# hexbot_LED.net
KiCad netlist of a schematic drawn in Altium Designer
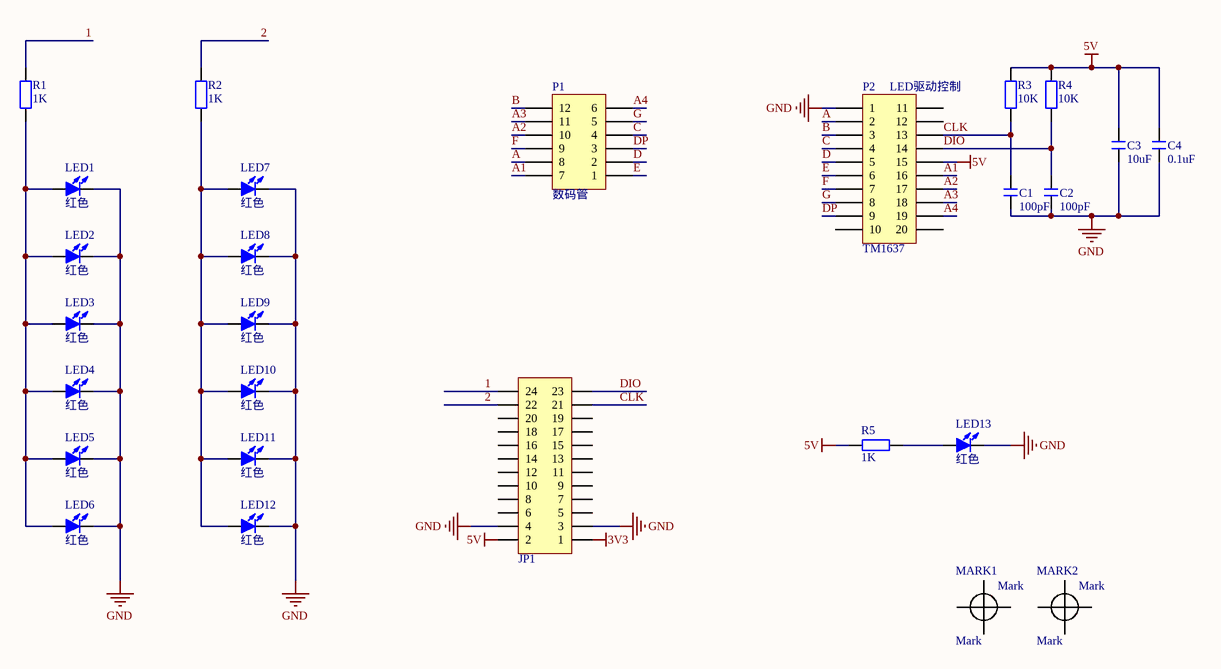
[diagram p0: hexbot_LED.SchDoc]

(export (version "E")
  (design (tool "Eeschema 10.0.6"))
  (components
    (comp (ref "C1")
      (value "100pF")
      (footprint "C 0603_L")
      (description "贴片电容")
      (libsource (lib "0.1 - 电阻-电容-电感") (part "C"))
    )
    (comp (ref "C2")
      (value "100pF")
      (footprint "C 0603_L")
      (description "贴片电容")
      (libsource (lib "0.1 - 电阻-电容-电感") (part "C"))
    )
    (comp (ref "C3")
      (value "10uF")
      (footprint "C 0603_L")
      (description "贴片电容")
      (libsource (lib "0.1 - 电阻-电容-电感") (part "C"))
    )
    (comp (ref "C4")
      (value "0.1uF")
      (footprint "C 0603_L")
      (description "贴片电容")
      (libsource (lib "0.1 - 电阻-电容-电感") (part "C"))
    )
    (comp (ref "JP1")
      (value "Header 2X11")
      (footprint "HDR2.54-WI-2x12P")
      (description "12*2P接插件")
      (fields (field (name "版权归属") "封装库来自淘宝卖家 ID：黄晶宝石"))
      (libsource (lib "5.4 - 接插件-脚距2.54 (100mil) ") (part "Header 12X2"))
    )
    (comp (ref "LED1")
      (value "红色")
      (footprint "LED 0603R")
      (description "贴片LED")
      (fields (field (name "版权归属") "封装库来自淘宝 ID：黄晶宝石"))
      (libsource (lib "0.3 - LED发光二极管") (part "LED-SMD"))
    )
    (comp (ref "LED2")
      (value "红色")
      (footprint "LED 0603R")
      (description "贴片LED")
      (fields (field (name "版权归属") "封装库来自淘宝 ID：黄晶宝石"))
      (libsource (lib "0.3 - LED发光二极管") (part "LED-SMD"))
    )
    (comp (ref "LED3")
      (value "红色")
      (footprint "LED 0603R")
      (description "贴片LED")
      (fields (field (name "版权归属") "封装库来自淘宝 ID：黄晶宝石"))
      (libsource (lib "0.3 - LED发光二极管") (part "LED-SMD"))
    )
    (comp (ref "LED4")
      (value "红色")
      (footprint "LED 0603R")
      (description "贴片LED")
      (fields (field (name "版权归属") "封装库来自淘宝 ID：黄晶宝石"))
      (libsource (lib "0.3 - LED发光二极管") (part "LED-SMD"))
    )
    (comp (ref "LED5")
      (value "红色")
      (footprint "LED 0603R")
      (description "贴片LED")
      (fields (field (name "版权归属") "封装库来自淘宝 ID：黄晶宝石"))
      (libsource (lib "0.3 - LED发光二极管") (part "LED-SMD"))
    )
    (comp (ref "LED6")
      (value "红色")
      (footprint "LED 0603R")
      (description "贴片LED")
      (fields (field (name "版权归属") "封装库来自淘宝 ID：黄晶宝石"))
      (libsource (lib "0.3 - LED发光二极管") (part "LED-SMD"))
    )
    (comp (ref "LED7")
      (value "红色")
      (footprint "LED 0603R")
      (description "贴片LED")
      (fields (field (name "版权归属") "封装库来自淘宝 ID：黄晶宝石"))
      (libsource (lib "0.3 - LED发光二极管") (part "LED-SMD"))
    )
    (comp (ref "LED8")
      (value "红色")
      (footprint "LED 0603R")
      (description "贴片LED")
      (fields (field (name "版权归属") "封装库来自淘宝 ID：黄晶宝石"))
      (libsource (lib "0.3 - LED发光二极管") (part "LED-SMD"))
    )
    (comp (ref "LED9")
      (value "红色")
      (footprint "LED 0603R")
      (description "贴片LED")
      (fields (field (name "版权归属") "封装库来自淘宝 ID：黄晶宝石"))
      (libsource (lib "0.3 - LED发光二极管") (part "LED-SMD"))
    )
    (comp (ref "LED10")
      (value "红色")
      (footprint "LED 0603R")
      (description "贴片LED")
      (fields (field (name "版权归属") "封装库来自淘宝 ID：黄晶宝石"))
      (libsource (lib "0.3 - LED发光二极管") (part "LED-SMD"))
    )
    (comp (ref "LED11")
      (value "红色")
      (footprint "LED 0603R")
      (description "贴片LED")
      (fields (field (name "版权归属") "封装库来自淘宝 ID：黄晶宝石"))
      (libsource (lib "0.3 - LED发光二极管") (part "LED-SMD"))
    )
    (comp (ref "LED12")
      (value "红色")
      (footprint "LED 0603R")
      (description "贴片LED")
      (fields (field (name "版权归属") "封装库来自淘宝 ID：黄晶宝石"))
      (libsource (lib "0.3 - LED发光二极管") (part "LED-SMD"))
    )
    (comp (ref "LED13")
      (value "红色")
      (footprint "LED 0603R")
      (description "贴片LED")
      (fields (field (name "版权归属") "封装库来自淘宝 ID：黄晶宝石"))
      (libsource (lib "0.3 - LED发光二极管") (part "LED-SMD"))
    )
    (comp (ref "MARK1") (value "Mark") (footprint "Mark:Mark") (libsource (lib "Mark") (part "Mark")))
    (comp (ref "MARK2") (value "Mark") (footprint "Mark:Mark") (libsource (lib "Mark") (part "Mark")))
    (comp (ref "P1")
      (value "数码管")
      (footprint "数码管")
      (description "Header, 6-Pin, Dual row")
      (fields (field (name "PUBLISHER") "Altium Limited"))
      (libsource (lib "Miscellaneous Connectors") (part "Header 6X2A"))
    )
    (comp (ref "P2")
      (value "TM1637")
      (footprint "TM1637封装")
      (description "Header, 10-Pin, Dual row")
      (fields (field (name "PUBLISHER") "Altium Limited"))
      (libsource (lib "Miscellaneous Connectors") (part "Header 10X2A"))
    )
    (comp (ref "R1")
      (value "1K")
      (footprint "R 0603_L")
      (description "贴片电阻")
      (fields (field (name "版权归属") "来自淘宝 ID：黄晶宝石"))
      (libsource (lib "0.1 - 电阻-电容-电感") (part "R"))
    )
    (comp (ref "R2")
      (value "1K")
      (footprint "R 0603_L")
      (description "贴片电阻")
      (fields (field (name "版权归属") "来自淘宝 ID：黄晶宝石"))
      (libsource (lib "0.1 - 电阻-电容-电感") (part "R"))
    )
    (comp (ref "R3")
      (value "10K")
      (footprint "R 0603_L")
      (description "贴片电阻")
      (fields (field (name "版权归属") "来自淘宝 ID：黄晶宝石"))
      (libsource (lib "0.1 - 电阻-电容-电感") (part "R"))
    )
    (comp (ref "R4")
      (value "10K")
      (footprint "R 0603_L")
      (description "贴片电阻")
      (fields (field (name "版权归属") "来自淘宝 ID：黄晶宝石"))
      (libsource (lib "0.1 - 电阻-电容-电感") (part "R"))
    )
    (comp (ref "R5")
      (value "1K")
      (footprint "R 0603_L")
      (description "贴片电阻")
      (fields (field (name "版权归属") "来自淘宝 ID：黄晶宝石"))
      (libsource (lib "0.1 - 电阻-电容-电感") (part "R"))
    )
  )
  (nets
    (net (code "1") (name "/1") (class "Default")
      (node (ref "JP1") (pin "24") (pinfunction "24_24") (pintype "passive"))
      (node (ref "R1") (pin "2") (pinfunction "2_2") (pintype "passive"))
    )
    (net (code "2") (name "/2") (class "Default")
      (node (ref "JP1") (pin "22") (pinfunction "22_22") (pintype "passive"))
      (node (ref "R2") (pin "2") (pinfunction "2_2") (pintype "passive"))
    )
    (net (code "3") (name "/A") (class "Default")
      (node (ref "P1") (pin "8") (pinfunction "8_8") (pintype "passive"))
      (node (ref "P2") (pin "2") (pinfunction "2_2") (pintype "passive"))
    )
    (net (code "4") (name "/A1") (class "Default")
      (node (ref "P1") (pin "7") (pinfunction "7_7") (pintype "passive"))
      (node (ref "P2") (pin "16") (pinfunction "16_16") (pintype "passive"))
    )
    (net (code "5") (name "/A2") (class "Default")
      (node (ref "P1") (pin "10") (pinfunction "10_10") (pintype "passive"))
      (node (ref "P2") (pin "17") (pinfunction "17_17") (pintype "passive"))
    )
    (net (code "6") (name "/A3") (class "Default")
      (node (ref "P1") (pin "11") (pinfunction "11_11") (pintype "passive"))
      (node (ref "P2") (pin "18") (pinfunction "18_18") (pintype "passive"))
    )
    (net (code "7") (name "/A4") (class "Default")
      (node (ref "P1") (pin "6") (pinfunction "6_6") (pintype "passive"))
      (node (ref "P2") (pin "19") (pinfunction "19_19") (pintype "passive"))
    )
    (net (code "8") (name "/B") (class "Default")
      (node (ref "P1") (pin "12") (pinfunction "12_12") (pintype "passive"))
      (node (ref "P2") (pin "3") (pinfunction "3_3") (pintype "passive"))
    )
    (net (code "9") (name "/C") (class "Default")
      (node (ref "P1") (pin "4") (pinfunction "4_4") (pintype "passive"))
      (node (ref "P2") (pin "4") (pinfunction "4_4") (pintype "passive"))
    )
    (net (code "10") (name "/CLK") (class "Default")
      (node (ref "C1") (pin "2") (pinfunction "2_2") (pintype "passive"))
      (node (ref "JP1") (pin "21") (pinfunction "21_21") (pintype "passive"))
      (node (ref "P2") (pin "13") (pinfunction "13_13") (pintype "passive"))
      (node (ref "R3") (pin "1") (pinfunction "1_1") (pintype "passive"))
    )
    (net (code "11") (name "/D") (class "Default")
      (node (ref "P1") (pin "2") (pinfunction "2_2") (pintype "passive"))
      (node (ref "P2") (pin "5") (pinfunction "5_5") (pintype "passive"))
    )
    (net (code "12") (name "/DIO") (class "Default")
      (node (ref "C2") (pin "2") (pinfunction "2_2") (pintype "passive"))
      (node (ref "JP1") (pin "23") (pinfunction "23_23") (pintype "passive"))
      (node (ref "P2") (pin "14") (pinfunction "14_14") (pintype "passive"))
      (node (ref "R4") (pin "1") (pinfunction "1_1") (pintype "passive"))
    )
    (net (code "13") (name "/DP") (class "Default")
      (node (ref "P1") (pin "3") (pinfunction "3_3") (pintype "passive"))
      (node (ref "P2") (pin "9") (pinfunction "9_9") (pintype "passive"))
    )
    (net (code "14") (name "/E") (class "Default")
      (node (ref "P1") (pin "1") (pinfunction "1_1") (pintype "passive"))
      (node (ref "P2") (pin "6") (pinfunction "6_6") (pintype "passive"))
    )
    (net (code "15") (name "/F") (class "Default")
      (node (ref "P1") (pin "9") (pinfunction "9_9") (pintype "passive"))
      (node (ref "P2") (pin "7") (pinfunction "7_7") (pintype "passive"))
    )
    (net (code "16") (name "/G") (class "Default")
      (node (ref "P1") (pin "5") (pinfunction "5_5") (pintype "passive"))
      (node (ref "P2") (pin "8") (pinfunction "8_8") (pintype "passive"))
    )
    (net (code "17") (name "3V3") (class "Default")
      (node (ref "JP1") (pin "1") (pinfunction "1_1") (pintype "passive"))
    )
    (net (code "18") (name "5V") (class "Default")
      (node (ref "C3") (pin "2") (pinfunction "2_2") (pintype "passive"))
      (node (ref "C4") (pin "2") (pinfunction "2_2") (pintype "passive"))
      (node (ref "JP1") (pin "2") (pinfunction "2_2") (pintype "passive"))
      (node (ref "P2") (pin "15") (pinfunction "15_15") (pintype "passive"))
      (node (ref "R3") (pin "2") (pinfunction "2_2") (pintype "passive"))
      (node (ref "R4") (pin "2") (pinfunction "2_2") (pintype "passive"))
      (node (ref "R5") (pin "2") (pinfunction "2_2") (pintype "passive"))
    )
    (net (code "19") (name "GND") (class "Default")
      (node (ref "C1") (pin "1") (pinfunction "1_1") (pintype "passive"))
      (node (ref "C2") (pin "1") (pinfunction "1_1") (pintype "passive"))
      (node (ref "C3") (pin "1") (pinfunction "1_1") (pintype "passive"))
      (node (ref "C4") (pin "1") (pinfunction "1_1") (pintype "passive"))
      (node (ref "JP1") (pin "3") (pinfunction "3_3") (pintype "passive"))
      (node (ref "JP1") (pin "4") (pinfunction "4_4") (pintype "passive"))
      (node (ref "LED1") (pin "2") (pinfunction "K_2") (pintype "passive"))
      (node (ref "LED10") (pin "2") (pinfunction "K_2") (pintype "passive"))
      (node (ref "LED11") (pin "2") (pinfunction "K_2") (pintype "passive"))
      (node (ref "LED12") (pin "2") (pinfunction "K_2") (pintype "passive"))
      (node (ref "LED13") (pin "2") (pinfunction "K_2") (pintype "passive"))
      (node (ref "LED2") (pin "2") (pinfunction "K_2") (pintype "passive"))
      (node (ref "LED3") (pin "2") (pinfunction "K_2") (pintype "passive"))
      (node (ref "LED4") (pin "2") (pinfunction "K_2") (pintype "passive"))
      (node (ref "LED5") (pin "2") (pinfunction "K_2") (pintype "passive"))
      (node (ref "LED6") (pin "2") (pinfunction "K_2") (pintype "passive"))
      (node (ref "LED7") (pin "2") (pinfunction "K_2") (pintype "passive"))
      (node (ref "LED8") (pin "2") (pinfunction "K_2") (pintype "passive"))
      (node (ref "LED9") (pin "2") (pinfunction "K_2") (pintype "passive"))
      (node (ref "P2") (pin "1") (pinfunction "1_1") (pintype "passive"))
    )
    (net (code "20") (name "Net-(LED1-A)") (class "Default")
      (node (ref "LED1") (pin "1") (pinfunction "A_1") (pintype "passive"))
      (node (ref "LED2") (pin "1") (pinfunction "A_1") (pintype "passive"))
      (node (ref "LED3") (pin "1") (pinfunction "A_1") (pintype "passive"))
      (node (ref "LED4") (pin "1") (pinfunction "A_1") (pintype "passive"))
      (node (ref "LED5") (pin "1") (pinfunction "A_1") (pintype "passive"))
      (node (ref "LED6") (pin "1") (pinfunction "A_1") (pintype "passive"))
      (node (ref "R1") (pin "1") (pinfunction "1_1") (pintype "passive"))
    )
    (net (code "21") (name "Net-(LED10-A)") (class "Default")
      (node (ref "LED10") (pin "1") (pinfunction "A_1") (pintype "passive"))
      (node (ref "LED11") (pin "1") (pinfunction "A_1") (pintype "passive"))
      (node (ref "LED12") (pin "1") (pinfunction "A_1") (pintype "passive"))
      (node (ref "LED7") (pin "1") (pinfunction "A_1") (pintype "passive"))
      (node (ref "LED8") (pin "1") (pinfunction "A_1") (pintype "passive"))
      (node (ref "LED9") (pin "1") (pinfunction "A_1") (pintype "passive"))
      (node (ref "R2") (pin "1") (pinfunction "1_1") (pintype "passive"))
    )
    (net (code "22") (name "Net-(LED13-A)") (class "Default")
      (node (ref "LED13") (pin "1") (pinfunction "A_1") (pintype "passive"))
      (node (ref "R5") (pin "1") (pinfunction "1_1") (pintype "passive"))
    )
    (net (code "23") (name "unconnected-(JP1-Pad5)") (class "Default")
      (node (ref "JP1") (pin "5") (pinfunction "5_5") (pintype "passive"))
    )
    (net (code "24") (name "unconnected-(JP1-Pad6)") (class "Default")
      (node (ref "JP1") (pin "6") (pinfunction "6_6") (pintype "passive"))
    )
    (net (code "25") (name "unconnected-(JP1-Pad7)") (class "Default")
      (node (ref "JP1") (pin "7") (pinfunction "7_7") (pintype "passive"))
    )
    (net (code "26") (name "unconnected-(JP1-Pad8)") (class "Default")
      (node (ref "JP1") (pin "8") (pinfunction "8_8") (pintype "passive"))
    )
    (net (code "27") (name "unconnected-(JP1-Pad9)") (class "Default")
      (node (ref "JP1") (pin "9") (pinfunction "9_9") (pintype "passive"))
    )
    (net (code "28") (name "unconnected-(JP1-Pad10)") (class "Default")
      (node (ref "JP1") (pin "10") (pinfunction "10_10") (pintype "passive"))
    )
    (net (code "29") (name "unconnected-(JP1-Pad11)") (class "Default")
      (node (ref "JP1") (pin "11") (pinfunction "11_11") (pintype "passive"))
    )
    (net (code "30") (name "unconnected-(JP1-Pad12)") (class "Default")
      (node (ref "JP1") (pin "12") (pinfunction "12_12") (pintype "passive"))
    )
    (net (code "31") (name "unconnected-(JP1-Pad13)") (class "Default")
      (node (ref "JP1") (pin "13") (pinfunction "13_13") (pintype "passive"))
    )
    (net (code "32") (name "unconnected-(JP1-Pad14)") (class "Default")
      (node (ref "JP1") (pin "14") (pinfunction "14_14") (pintype "passive"))
    )
    (net (code "33") (name "unconnected-(JP1-Pad15)") (class "Default")
      (node (ref "JP1") (pin "15") (pinfunction "15_15") (pintype "passive"))
    )
    (net (code "34") (name "unconnected-(JP1-Pad16)") (class "Default")
      (node (ref "JP1") (pin "16") (pinfunction "16_16") (pintype "passive"))
    )
    (net (code "35") (name "unconnected-(JP1-Pad17)") (class "Default")
      (node (ref "JP1") (pin "17") (pinfunction "17_17") (pintype "passive"))
    )
    (net (code "36") (name "unconnected-(JP1-Pad18)") (class "Default")
      (node (ref "JP1") (pin "18") (pinfunction "18_18") (pintype "passive"))
    )
    (net (code "37") (name "unconnected-(JP1-Pad19)") (class "Default")
      (node (ref "JP1") (pin "19") (pinfunction "19_19") (pintype "passive"))
    )
    (net (code "38") (name "unconnected-(JP1-Pad20)") (class "Default")
      (node (ref "JP1") (pin "20") (pinfunction "20_20") (pintype "passive"))
    )
    (net (code "39") (name "unconnected-(P2-Pad10)") (class "Default")
      (node (ref "P2") (pin "10") (pinfunction "10_10") (pintype "passive"))
    )
    (net (code "40") (name "unconnected-(P2-Pad11)") (class "Default")
      (node (ref "P2") (pin "11") (pinfunction "11_11") (pintype "passive"))
    )
    (net (code "41") (name "unconnected-(P2-Pad12)") (class "Default")
      (node (ref "P2") (pin "12") (pinfunction "12_12") (pintype "passive"))
    )
    (net (code "42") (name "unconnected-(P2-Pad20)") (class "Default")
      (node (ref "P2") (pin "20") (pinfunction "20_20") (pintype "passive"))
    )
  )
)
